# 3V3a.net
KiCad netlist of a schematic drawn in Altium Designer
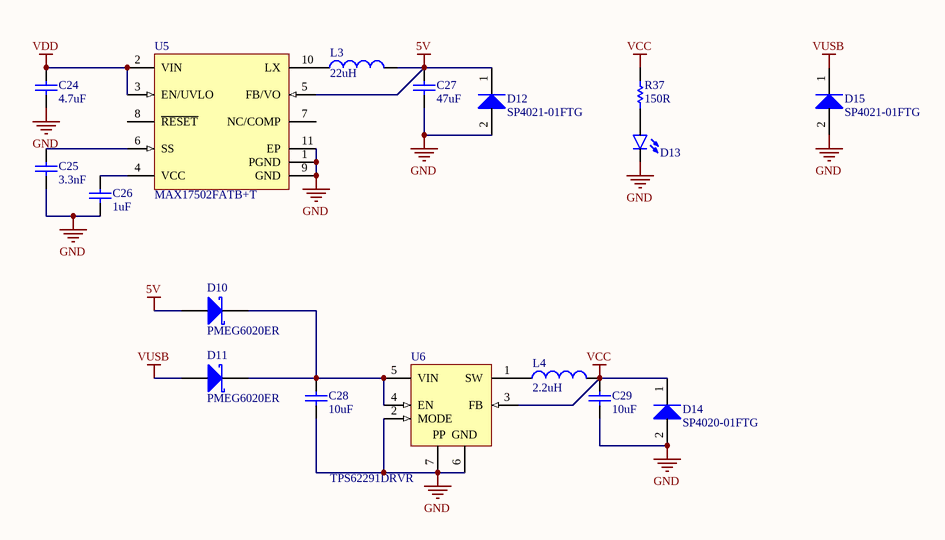
[diagram p0: 3V3a.SchDoc]

(export (version "E")
  (design (tool "Eeschema 10.0.6"))
  (components
    (comp (ref "C24")
      (value "4.7uF")
      (footprint "C1210[3225X200]")
      (description "4.7uF 100V 10% 1210 (3225 Metric)")
      (fields (field (name "TOLERANCE") "10%") (field (name "PARTNUMBER") "GRJ32DC72A475KE11L"))
      (libsource (lib "Capacitors") (part "CAP_4.7uF_100V_1210_10%"))
    )
    (comp (ref "C25")
      (value "3.3nF")
      (footprint "C0402[1005X55]")
      (description "3.3nF 50V 10% 0402 (1005 Metric)")
      (fields (field (name "TOLERANCE") "10%") (field (name "PARTNUMBER") "GRM155R71H332KA01D"))
      (libsource (lib "Capacitors") (part "CAP_3.3nF_50V_0402_10%"))
    )
    (comp (ref "C26")
      (value "1uF")
      (footprint "C0402[1005X55]")
      (description "1uF 6.3V 10% 0402 (1005 Metric)")
      (fields (field (name "TOLERANCE") "10%") (field (name "PARTNUMBER") "GRM155R70J105KA12D"))
      (libsource (lib "Capacitors") (part "CAP_1uF_6.3V_0402_10%"))
    )
    (comp (ref "C27")
      (value "47uF")
      (footprint "C1210[3225X250]")
      (description "47uF 6.3V 10% 1210 (3225 Metric)")
      (fields (field (name "TOLERANCE") "10%") (field (name "PARTNUMBER") "GRM32ER70J476KE20L"))
      (libsource (lib "Capacitors") (part "CAP_47uF_6.3V_1210_10%"))
    )
    (comp (ref "C28")
      (value "10uF")
      (footprint "C0402[1005X55]")
      (description "10uF 6.3V 20% 0402 (1005 Metric)")
      (fields (field (name "TOLERANCE") "20%") (field (name "PARTNUMBER") "GRM155R60J106ME44D"))
      (libsource (lib "Capacitors") (part "CAP_10uF_6.3V_0402_20%"))
    )
    (comp (ref "C29")
      (value "10uF")
      (footprint "C0402[1005X55]")
      (description "10uF 6.3V 20% 0402 (1005 Metric)")
      (fields (field (name "TOLERANCE") "20%") (field (name "PARTNUMBER") "GRM155R60J106ME44D"))
      (libsource (lib "Capacitors") (part "CAP_10uF_6.3V_0402_20%"))
    )
    (comp (ref "D10")
      (value "PMEG6020ER")
      (footprint "SOD-123")
      (fields (field (name "PARTNUMBER") "PMEG6020ER,115") (field (name "MANUFACTURER") "NXP Semiconductors"))
      (libsource (lib "Diodes") (part "PMEG6020ER"))
    )
    (comp (ref "D11")
      (value "PMEG6020ER")
      (footprint "SOD-123")
      (fields (field (name "PARTNUMBER") "PMEG6020ER,115") (field (name "MANUFACTURER") "NXP Semiconductors"))
      (libsource (lib "Diodes") (part "PMEG6020ER"))
    )
    (comp (ref "D12")
      (value "SP4021-01FTG")
      (footprint "SOD-323")
      (fields (field (name "MANUFACTURER") "Littelfuse"))
      (libsource (lib "Diodes") (part "SP4021-01FTG"))
    )
    (comp (ref "D13")
      (value "LED_0603_GREEN_5mA")
      (footprint "LED0603")
      (fields (field (name "PARTNUMBER") "LTST-C193TGKT-5A") (field (name "MANUFACTURER") "Lite-On Inc."))
      (libsource (lib "LEDs") (part "LED_0603_GREEN_5mA"))
    )
    (comp (ref "D14")
      (value "SP4020-01FTG")
      (footprint "SOD323")
      (fields (field (name "MANUFACTURER") "Littelfuse"))
      (libsource (lib "Diodes") (part "SP4020-01FTG"))
    )
    (comp (ref "D15")
      (value "SP4021-01FTG")
      (footprint "SOD-323")
      (fields (field (name "MANUFACTURER") "Littelfuse"))
      (libsource (lib "Diodes-TVS") (part "SP4021-01FTG"))
    )
    (comp (ref "L3")
      (value "22uH")
      (footprint "SDR0604")
      (description "22uH 30% 1.1A 0604")
      (fields (field (name "PARTNUMBER") "SDR0604-220YL") (field (name "MANUFACTURER") "Bourns"))
      (libsource (lib "Inductors") (part "SDR0604-220YL"))
    )
    (comp (ref "L4")
      (value "2.2uH")
      (footprint "IND0805")
      (description "2.2uH 20% 1.7A 0805")
      (fields (field (name "PARTNUMBER") "LQM21PN2R2MGHL") (field (name "MANUFACTURER") "Murata"))
      (libsource (lib "Inductors") (part "IND_2.2uH_1.7A_0805_20%"))
    )
    (comp (ref "R37")
      (value "150R")
      (footprint "R0402[1005]")
      (description "150R 0.063W 1% 0402 (1005 Metric)")
      (fields (field (name "POWER") "0.063W") (field (name "TOLERANCE") "1%"))
      (libsource (lib "Resistors") (part "RES_150R_0402_1%"))
    )
    (comp (ref "U5")
      (value "MAX17502FATB+T")
      (footprint "TDFN-10-EP")
      (fields (field (name "MANUFACTURER") "Maxim Integrated"))
      (libsource (lib "ICs") (part "MAX17502FATB+T"))
    )
    (comp (ref "U6")
      (value "TPS62291DRVR")
      (footprint "WSON-6")
      (description "Voltage Regulators - Switching Regulators 2.25MHz 1A Step-Down Cnvrtr 3.3V Output")
      (fields (field (name "MANUFACTURER") "Texas Instruments"))
      (libsource (lib "ICs") (part "TPS62291DRVR"))
    )
  )
  (nets
    (net (code "1") (name "5V") (class "Default")
      (node (ref "C27") (pin "2") (pinfunction "2_2") (pintype "passive"))
      (node (ref "D10") (pin "2") (pinfunction "A_2") (pintype "passive"))
      (node (ref "D12") (pin "1") (pinfunction "K_1") (pintype "passive"))
      (node (ref "L3") (pin "2") (pinfunction "2_2") (pintype "passive"))
      (node (ref "U5") (pin "5") (pinfunction "FB/VO_5") (pintype "input"))
    )
    (net (code "2") (name "GND") (class "Default")
      (node (ref "C24") (pin "1") (pinfunction "1_1") (pintype "passive"))
      (node (ref "C25") (pin "1") (pinfunction "1_1") (pintype "passive"))
      (node (ref "C26") (pin "1") (pinfunction "1_1") (pintype "passive"))
      (node (ref "C27") (pin "1") (pinfunction "1_1") (pintype "passive"))
      (node (ref "C28") (pin "1") (pinfunction "1_1") (pintype "passive"))
      (node (ref "C29") (pin "1") (pinfunction "1_1") (pintype "passive"))
      (node (ref "D12") (pin "2") (pinfunction "A_2") (pintype "passive"))
      (node (ref "D13") (pin "C") (pinfunction "C_C") (pintype "passive"))
      (node (ref "D14") (pin "2") (pinfunction "A_2") (pintype "passive"))
      (node (ref "D15") (pin "2") (pinfunction "A_2") (pintype "passive"))
      (node (ref "U5") (pin "1") (pinfunction "PGND_1") (pintype "power_in"))
      (node (ref "U5") (pin "11") (pinfunction "EP_11") (pintype "power_in"))
      (node (ref "U5") (pin "9") (pinfunction "GND_9") (pintype "power_in"))
      (node (ref "U6") (pin "2") (pinfunction "MODE_2") (pintype "input"))
      (node (ref "U6") (pin "6") (pinfunction "GND_6") (pintype "power_in"))
      (node (ref "U6") (pin "7") (pinfunction "EP_7") (pintype "passive"))
    )
    (net (code "3") (name "Net-(D10-K)") (class "Default")
      (node (ref "C28") (pin "2") (pinfunction "2_2") (pintype "passive"))
      (node (ref "D10") (pin "1") (pinfunction "K_1") (pintype "passive"))
      (node (ref "D11") (pin "1") (pinfunction "K_1") (pintype "passive"))
      (node (ref "U6") (pin "4") (pinfunction "EN_4") (pintype "input"))
      (node (ref "U6") (pin "5") (pinfunction "VIN_5") (pintype "power_in"))
    )
    (net (code "4") (name "Net-(D13-PadA)") (class "Default")
      (node (ref "D13") (pin "A") (pinfunction "A_A") (pintype "passive"))
      (node (ref "R37") (pin "1") (pinfunction "1_1") (pintype "passive"))
    )
    (net (code "5") (name "Net-(U5-LX)") (class "Default")
      (node (ref "L3") (pin "1") (pinfunction "1_1") (pintype "passive"))
      (node (ref "U5") (pin "10") (pinfunction "LX_10") (pintype "passive"))
    )
    (net (code "6") (name "Net-(U5-SS)") (class "Default")
      (node (ref "C25") (pin "2") (pinfunction "2_2") (pintype "passive"))
      (node (ref "U5") (pin "6") (pinfunction "SS_6") (pintype "input"))
    )
    (net (code "7") (name "Net-(U5-VCC)") (class "Default")
      (node (ref "C26") (pin "2") (pinfunction "2_2") (pintype "passive"))
      (node (ref "U5") (pin "4") (pinfunction "VCC_4") (pintype "power_in"))
    )
    (net (code "8") (name "Net-(U6-SW)") (class "Default")
      (node (ref "L4") (pin "1") (pinfunction "1_1") (pintype "passive"))
      (node (ref "U6") (pin "1") (pinfunction "SW_1") (pintype "power_in"))
    )
    (net (code "9") (name "VCC") (class "Default")
      (node (ref "C29") (pin "2") (pinfunction "2_2") (pintype "passive"))
      (node (ref "D14") (pin "1") (pinfunction "K_1") (pintype "passive"))
      (node (ref "L4") (pin "2") (pinfunction "2_2") (pintype "passive"))
      (node (ref "R37") (pin "2") (pinfunction "2_2") (pintype "passive"))
      (node (ref "U6") (pin "3") (pinfunction "FB_3") (pintype "input"))
    )
    (net (code "10") (name "VDD") (class "Default")
      (node (ref "C24") (pin "2") (pinfunction "2_2") (pintype "passive"))
      (node (ref "U5") (pin "2") (pinfunction "VIN_2") (pintype "power_in"))
      (node (ref "U5") (pin "3") (pinfunction "EN/UVLO_3") (pintype "input"))
    )
    (net (code "11") (name "VUSB") (class "Default")
      (node (ref "D11") (pin "2") (pinfunction "A_2") (pintype "passive"))
      (node (ref "D15") (pin "1") (pinfunction "K_1") (pintype "passive"))
    )
    (net (code "12") (name "unconnected-(U5-NC{slash}COMP-Pad7)") (class "Default")
      (node (ref "U5") (pin "7") (pinfunction "NC/COMP_7") (pintype "passive"))
    )
    (net (code "13") (name "unconnected-(U5-~{RESET}-Pad8)") (class "Default")
      (node (ref "U5") (pin "8") (pinfunction "~{RESET}_8") (pintype "open_collector"))
    )
  )
)
